# Radio_Module.net
KiCad netlist of a schematic drawn in Altium Designer
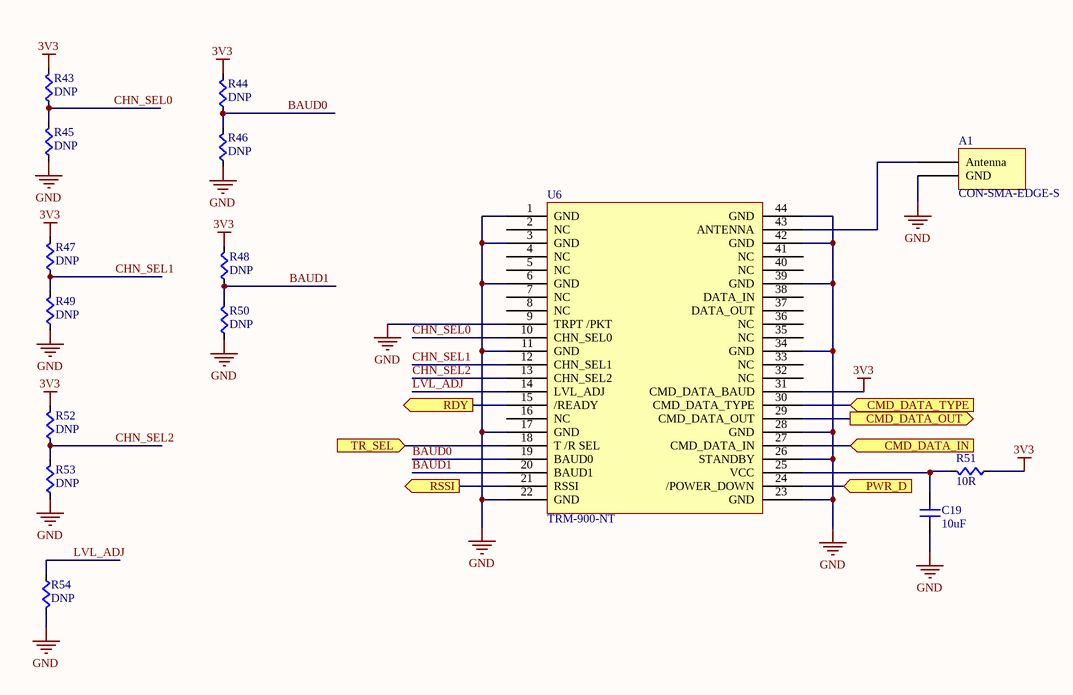
[diagram p0: Radio Module.SchDoc]

(export (version "E")
  (design (tool "Eeschema 10.0.6"))
  (components
    (comp (ref "A1")
      (value "CON-SMA-EDGE-S")
      (footprint "CON-SMA-EDGE-S")
      (description "CONN SMA JACK STR EDGE MNT")
      (libsource (lib "SubjuGator8") (part "CON-SMA-EDGE-S"))
    )
    (comp (ref "C19")
      (value "10uF")
      (footprint "CAPC0603")
      (fields (field (name "Comment") "Cap"))
      (libsource (lib "SubjuGator8") (part "Cap"))
    )
    (comp (ref "R43")
      (value "DNP")
      (footprint "RES0603")
      (fields (field (name "Comment") "Res"))
      (libsource (lib "SubjuGator8") (part "Res"))
    )
    (comp (ref "R44")
      (value "DNP")
      (footprint "RES0603")
      (fields (field (name "Comment") "Res"))
      (libsource (lib "SubjuGator8") (part "Res"))
    )
    (comp (ref "R45")
      (value "DNP")
      (footprint "RES0603")
      (fields (field (name "Comment") "Res"))
      (libsource (lib "SubjuGator8") (part "Res"))
    )
    (comp (ref "R46")
      (value "DNP")
      (footprint "RES0603")
      (fields (field (name "Comment") "Res"))
      (libsource (lib "SubjuGator8") (part "Res"))
    )
    (comp (ref "R47")
      (value "DNP")
      (footprint "RES0603")
      (fields (field (name "Comment") "Res"))
      (libsource (lib "SubjuGator8") (part "Res"))
    )
    (comp (ref "R48")
      (value "DNP")
      (footprint "RES0603")
      (fields (field (name "Comment") "Res"))
      (libsource (lib "SubjuGator8") (part "Res"))
    )
    (comp (ref "R49")
      (value "DNP")
      (footprint "RES0603")
      (fields (field (name "Comment") "Res"))
      (libsource (lib "SubjuGator8") (part "Res"))
    )
    (comp (ref "R50")
      (value "DNP")
      (footprint "RES0603")
      (fields (field (name "Comment") "Res"))
      (libsource (lib "SubjuGator8") (part "Res"))
    )
    (comp (ref "R51")
      (value "10R")
      (footprint "RES0603")
      (fields (field (name "Comment") "Res"))
      (libsource (lib "SubjuGator8") (part "Res"))
    )
    (comp (ref "R52")
      (value "DNP")
      (footprint "RES0603")
      (fields (field (name "Comment") "Res"))
      (libsource (lib "SubjuGator8") (part "Res"))
    )
    (comp (ref "R53")
      (value "DNP")
      (footprint "RES0603")
      (fields (field (name "Comment") "Res"))
      (libsource (lib "SubjuGator8") (part "Res"))
    )
    (comp (ref "R54")
      (value "DNP")
      (footprint "RES0603")
      (fields (field (name "Comment") "Res"))
      (libsource (lib "SubjuGator8") (part "Res"))
    )
    (comp (ref "U6")
      (value "TRM-900-NT")
      (footprint "TRM-900-NT")
      (description "RF TXRX MODULE ISM<1GHZ")
      (libsource (lib "SubjuGator8") (part "TRM-900-NT"))
    )
  )
  (nets
    (net (code "1") (name "/BAUD0") (class "Default")
      (node (ref "R44") (pin "2") (pinfunction "B_2") (pintype "passive"))
      (node (ref "R46") (pin "1") (pinfunction "A_1") (pintype "passive"))
      (node (ref "U6") (pin "19") (pinfunction "BAUD0_19") (pintype "passive"))
    )
    (net (code "2") (name "/BAUD1") (class "Default")
      (node (ref "R48") (pin "2") (pinfunction "B_2") (pintype "passive"))
      (node (ref "R50") (pin "1") (pinfunction "A_1") (pintype "passive"))
      (node (ref "U6") (pin "20") (pinfunction "BAUD1_20") (pintype "passive"))
    )
    (net (code "3") (name "/CHN_SEL0") (class "Default")
      (node (ref "R43") (pin "2") (pinfunction "B_2") (pintype "passive"))
      (node (ref "R45") (pin "1") (pinfunction "A_1") (pintype "passive"))
      (node (ref "U6") (pin "10") (pinfunction "CHN_SEL0_10") (pintype "passive"))
    )
    (net (code "4") (name "/CHN_SEL1") (class "Default")
      (node (ref "R47") (pin "2") (pinfunction "B_2") (pintype "passive"))
      (node (ref "R49") (pin "1") (pinfunction "A_1") (pintype "passive"))
      (node (ref "U6") (pin "12") (pinfunction "CHN_SEL1_12") (pintype "passive"))
    )
    (net (code "5") (name "/CHN_SEL2") (class "Default")
      (node (ref "R52") (pin "2") (pinfunction "B_2") (pintype "passive"))
      (node (ref "R53") (pin "1") (pinfunction "A_1") (pintype "passive"))
      (node (ref "U6") (pin "13") (pinfunction "CHN_SEL2_13") (pintype "passive"))
    )
    (net (code "6") (name "/CMD_DATA_IN") (class "Default")
      (node (ref "U6") (pin "27") (pinfunction "CMD_DATA_IN_27") (pintype "passive"))
    )
    (net (code "7") (name "/CMD_DATA_OUT") (class "Default")
      (node (ref "U6") (pin "29") (pinfunction "CMD_DATA_OUT_29") (pintype "passive"))
    )
    (net (code "8") (name "/CMD_DATA_TYPE") (class "Default")
      (node (ref "U6") (pin "30") (pinfunction "CMD_DATA_TYPE_30") (pintype "passive"))
    )
    (net (code "9") (name "/LVL_ADJ") (class "Default")
      (node (ref "R54") (pin "2") (pinfunction "B_2") (pintype "passive"))
      (node (ref "U6") (pin "14") (pinfunction "LVL_ADJ_14") (pintype "passive"))
    )
    (net (code "10") (name "/PWR_D") (class "Default")
      (node (ref "U6") (pin "24") (pinfunction "/POWER_DOWN_24") (pintype "passive"))
    )
    (net (code "11") (name "/RDY") (class "Default")
      (node (ref "U6") (pin "15") (pinfunction "/READY_15") (pintype "passive"))
    )
    (net (code "12") (name "/RSSI") (class "Default")
      (node (ref "U6") (pin "21") (pinfunction "RSSI_21") (pintype "passive"))
    )
    (net (code "13") (name "/TR_SEL") (class "Default")
      (node (ref "U6") (pin "18") (pinfunction "T_/R_SEL_18") (pintype "passive"))
    )
    (net (code "14") (name "3V3") (class "Default")
      (node (ref "R43") (pin "1") (pinfunction "A_1") (pintype "passive"))
      (node (ref "R44") (pin "1") (pinfunction "A_1") (pintype "passive"))
      (node (ref "R47") (pin "1") (pinfunction "A_1") (pintype "passive"))
      (node (ref "R48") (pin "1") (pinfunction "A_1") (pintype "passive"))
      (node (ref "R51") (pin "2") (pinfunction "B_2") (pintype "passive"))
      (node (ref "R52") (pin "1") (pinfunction "A_1") (pintype "passive"))
      (node (ref "U6") (pin "31") (pinfunction "CMD_DATA_BAUD_31") (pintype "passive"))
    )
    (net (code "15") (name "GND") (class "Default")
      (node (ref "A1") (pin "1") (pinfunction "GND_1") (pintype "passive"))
      (node (ref "C19") (pin "2") (pinfunction "B_2") (pintype "passive"))
      (node (ref "R45") (pin "2") (pinfunction "B_2") (pintype "passive"))
      (node (ref "R46") (pin "2") (pinfunction "B_2") (pintype "passive"))
      (node (ref "R49") (pin "2") (pinfunction "B_2") (pintype "passive"))
      (node (ref "R50") (pin "2") (pinfunction "B_2") (pintype "passive"))
      (node (ref "R53") (pin "2") (pinfunction "B_2") (pintype "passive"))
      (node (ref "R54") (pin "1") (pinfunction "A_1") (pintype "passive"))
      (node (ref "U6") (pin "1") (pinfunction "GND_1") (pintype "passive"))
      (node (ref "U6") (pin "11") (pinfunction "GND_11") (pintype "passive"))
      (node (ref "U6") (pin "17") (pinfunction "GND_17") (pintype "passive"))
      (node (ref "U6") (pin "22") (pinfunction "GND_22") (pintype "passive"))
      (node (ref "U6") (pin "23") (pinfunction "GND_23") (pintype "passive"))
      (node (ref "U6") (pin "26") (pinfunction "STANDBY_26") (pintype "passive"))
      (node (ref "U6") (pin "28") (pinfunction "GND_28") (pintype "passive"))
      (node (ref "U6") (pin "3") (pinfunction "GND_3") (pintype "passive"))
      (node (ref "U6") (pin "34") (pinfunction "GND_34") (pintype "passive"))
      (node (ref "U6") (pin "39") (pinfunction "GND_39") (pintype "passive"))
      (node (ref "U6") (pin "42") (pinfunction "GND_42") (pintype "passive"))
      (node (ref "U6") (pin "44") (pinfunction "GND_44") (pintype "passive"))
      (node (ref "U6") (pin "6") (pinfunction "GND_6") (pintype "passive"))
      (node (ref "U6") (pin "9") (pinfunction "TRPT_/PKT_9") (pintype "passive"))
    )
    (net (code "16") (name "Net-(A1-Antenna)") (class "Default")
      (node (ref "A1") (pin "0") (pinfunction "Antenna_0") (pintype "passive"))
      (node (ref "U6") (pin "43") (pinfunction "ANTENNA_43") (pintype "passive"))
    )
    (net (code "17") (name "Net-(C19-A)") (class "Default")
      (node (ref "C19") (pin "1") (pinfunction "A_1") (pintype "passive"))
      (node (ref "R51") (pin "1") (pinfunction "A_1") (pintype "passive"))
      (node (ref "U6") (pin "25") (pinfunction "VCC_25") (pintype "passive"))
    )
    (net (code "18") (name "unconnected-(U6-DATA_IN-Pad38)") (class "Default")
      (node (ref "U6") (pin "38") (pinfunction "DATA_IN_38") (pintype "passive"))
    )
    (net (code "19") (name "unconnected-(U6-DATA_OUT-Pad37)") (class "Default")
      (node (ref "U6") (pin "37") (pinfunction "DATA_OUT_37") (pintype "passive"))
    )
    (net (code "20") (name "unconnected-(U6-NC-Pad2)") (class "Default")
      (node (ref "U6") (pin "2") (pinfunction "NC_2") (pintype "passive"))
    )
    (net (code "21") (name "unconnected-(U6-NC-Pad4)") (class "Default")
      (node (ref "U6") (pin "4") (pinfunction "NC_4") (pintype "passive"))
    )
    (net (code "22") (name "unconnected-(U6-NC-Pad5)") (class "Default")
      (node (ref "U6") (pin "5") (pinfunction "NC_5") (pintype "passive"))
    )
    (net (code "23") (name "unconnected-(U6-NC-Pad7)") (class "Default")
      (node (ref "U6") (pin "7") (pinfunction "NC_7") (pintype "passive"))
    )
    (net (code "24") (name "unconnected-(U6-NC-Pad8)") (class "Default")
      (node (ref "U6") (pin "8") (pinfunction "NC_8") (pintype "passive"))
    )
    (net (code "25") (name "unconnected-(U6-NC-Pad16)") (class "Default")
      (node (ref "U6") (pin "16") (pinfunction "NC_16") (pintype "passive"))
    )
    (net (code "26") (name "unconnected-(U6-NC-Pad32)") (class "Default")
      (node (ref "U6") (pin "32") (pinfunction "NC_32") (pintype "passive"))
    )
    (net (code "27") (name "unconnected-(U6-NC-Pad33)") (class "Default")
      (node (ref "U6") (pin "33") (pinfunction "NC_33") (pintype "passive"))
    )
    (net (code "28") (name "unconnected-(U6-NC-Pad35)") (class "Default")
      (node (ref "U6") (pin "35") (pinfunction "NC_35") (pintype "passive"))
    )
    (net (code "29") (name "unconnected-(U6-NC-Pad36)") (class "Default")
      (node (ref "U6") (pin "36") (pinfunction "NC_36") (pintype "passive"))
    )
    (net (code "30") (name "unconnected-(U6-NC-Pad40)") (class "Default")
      (node (ref "U6") (pin "40") (pinfunction "NC_40") (pintype "passive"))
    )
    (net (code "31") (name "unconnected-(U6-NC-Pad41)") (class "Default")
      (node (ref "U6") (pin "41") (pinfunction "NC_41") (pintype "passive"))
    )
  )
)
